# liftsensor.net
KiCad netlist of a schematic drawn in EAGLE
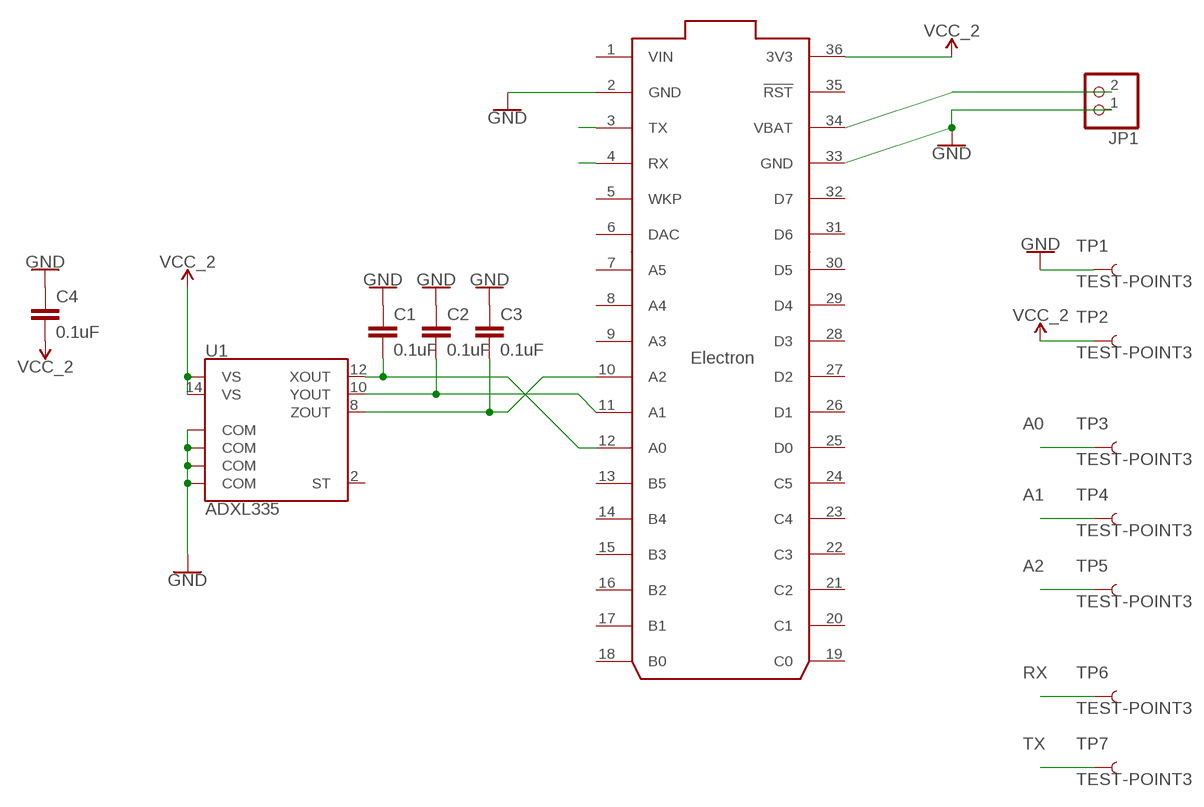
[diagram p0: schematic, sheet 1]

(export (version "E")
  (design (tool "Eeschema 10.0.6"))
  (components
    (comp (ref "C1")
      (value "0.1uF")
      (footprint "eagle-import:0603")
      (libsource (lib "eagle-import") (part "0.1UF-0603-25V-5%"))
    )
    (comp (ref "C2")
      (value "0.1uF")
      (footprint "eagle-import:0603")
      (libsource (lib "eagle-import") (part "0.1UF-0603-25V-5%"))
    )
    (comp (ref "C3")
      (value "0.1uF")
      (footprint "eagle-import:0603")
      (libsource (lib "eagle-import") (part "0.1UF-0603-25V-5%"))
    )
    (comp (ref "C4")
      (value "0.1uF")
      (footprint "eagle-import:0603")
      (libsource (lib "eagle-import") (part "0.1UF-0603-25V-5%"))
    )
    (comp (ref "EL")
      (value "ELECTRON_WITH_HEADERS")
      (footprint "eagle-import:ELECTRON")
      (libsource (lib "eagle-import") (part "ELECTRON_WITH_HEADERS"))
    )
    (comp (ref "JP1")
      (value "PINHD-1X2/90")
      (footprint "eagle-import:1X02_90")
      (libsource (lib "eagle-import") (part "PINHD-1X2/90"))
    )
    (comp (ref "TP1")
      (value "TEST-POINT3")
      (footprint "eagle-import:PAD.03X.03")
      (libsource (lib "eagle-import") (part "TEST-POINT3"))
    )
    (comp (ref "TP2")
      (value "TEST-POINT3")
      (footprint "eagle-import:PAD.03X.03")
      (libsource (lib "eagle-import") (part "TEST-POINT3"))
    )
    (comp (ref "TP3")
      (value "TEST-POINT3")
      (footprint "eagle-import:PAD.03X.03")
      (libsource (lib "eagle-import") (part "TEST-POINT3"))
    )
    (comp (ref "TP4")
      (value "TEST-POINT3")
      (footprint "eagle-import:PAD.03X.03")
      (libsource (lib "eagle-import") (part "TEST-POINT3"))
    )
    (comp (ref "TP5")
      (value "TEST-POINT3")
      (footprint "eagle-import:PAD.03X.03")
      (libsource (lib "eagle-import") (part "TEST-POINT3"))
    )
    (comp (ref "TP6")
      (value "TEST-POINT3")
      (footprint "eagle-import:PAD.03X.03")
      (libsource (lib "eagle-import") (part "TEST-POINT3"))
    )
    (comp (ref "TP7")
      (value "TEST-POINT3")
      (footprint "eagle-import:PAD.03X.03")
      (libsource (lib "eagle-import") (part "TEST-POINT3"))
    )
    (comp (ref "U1")
      (value "ADXL335")
      (footprint "eagle-import:LFCSP-16-4X4")
      (libsource (lib "eagle-import") (part "ADXL335"))
    )
  )
  (nets
    (net (code "1") (name "/A0") (class "Default")
      (node (ref "C1") (pin "2") (pinfunction "2_2") (pintype "passive"))
      (node (ref "EL") (pin "12") (pinfunction "A0_12") (pintype "bidirectional"))
      (node (ref "TP3") (pin "P$1") (pinfunction "1_P$1") (pintype "bidirectional"))
      (node (ref "U1") (pin "12") (pinfunction "XOUT_12") (pintype "bidirectional"))
    )
    (net (code "2") (name "/A1") (class "Default")
      (node (ref "C2") (pin "2") (pinfunction "2_2") (pintype "passive"))
      (node (ref "EL") (pin "11") (pinfunction "A1_11") (pintype "bidirectional"))
      (node (ref "TP4") (pin "P$1") (pinfunction "1_P$1") (pintype "bidirectional"))
      (node (ref "U1") (pin "10") (pinfunction "YOUT_10") (pintype "bidirectional"))
    )
    (net (code "3") (name "/A2") (class "Default")
      (node (ref "C3") (pin "2") (pinfunction "2_2") (pintype "passive"))
      (node (ref "EL") (pin "10") (pinfunction "A2_10") (pintype "bidirectional"))
      (node (ref "TP5") (pin "P$1") (pinfunction "1_P$1") (pintype "bidirectional"))
      (node (ref "U1") (pin "8") (pinfunction "ZOUT_8") (pintype "bidirectional"))
    )
    (net (code "4") (name "/RX") (class "Default")
      (node (ref "EL") (pin "4") (pinfunction "RX_4") (pintype "bidirectional"))
      (node (ref "TP6") (pin "P$1") (pinfunction "1_P$1") (pintype "bidirectional"))
    )
    (net (code "5") (name "/TX") (class "Default")
      (node (ref "EL") (pin "3") (pinfunction "TX_3") (pintype "bidirectional"))
      (node (ref "TP7") (pin "P$1") (pinfunction "1_P$1") (pintype "bidirectional"))
    )
    (net (code "6") (name "/VIN") (class "Default")
      (node (ref "EL") (pin "1") (pinfunction "VIN_1") (pintype "power_in"))
    )
    (net (code "7") (name "GND") (class "Default")
      (node (ref "C1") (pin "1") (pinfunction "1_1") (pintype "passive"))
      (node (ref "C2") (pin "1") (pinfunction "1_1") (pintype "passive"))
      (node (ref "C3") (pin "1") (pinfunction "1_1") (pintype "passive"))
      (node (ref "C4") (pin "1") (pinfunction "1_1") (pintype "passive"))
      (node (ref "EL") (pin "2") (pinfunction "GND_2") (pintype "power_in"))
      (node (ref "EL") (pin "33") (pinfunction "GND_33") (pintype "power_in"))
      (node (ref "JP1") (pin "1") (pinfunction "1_1") (pintype "passive"))
      (node (ref "TP1") (pin "P$1") (pinfunction "1_P$1") (pintype "bidirectional"))
      (node (ref "U1") (pin "3") (pinfunction "COM_3") (pintype "bidirectional"))
      (node (ref "U1") (pin "5") (pinfunction "COM_5") (pintype "bidirectional"))
      (node (ref "U1") (pin "6") (pinfunction "COM_6") (pintype "bidirectional"))
      (node (ref "U1") (pin "7") (pinfunction "COM_7") (pintype "bidirectional"))
    )
    (net (code "8") (name "Net-(EL-VBAT)") (class "Default")
      (node (ref "EL") (pin "34") (pinfunction "VBAT_34") (pintype "power_in"))
      (node (ref "JP1") (pin "2") (pinfunction "2_2") (pintype "passive"))
    )
    (net (code "9") (name "VCC_2") (class "Default")
      (node (ref "C4") (pin "2") (pinfunction "2_2") (pintype "passive"))
      (node (ref "EL") (pin "36") (pinfunction "3V3_36") (pintype "power_in"))
      (node (ref "TP2") (pin "P$1") (pinfunction "1_P$1") (pintype "bidirectional"))
      (node (ref "U1") (pin "14") (pinfunction "VS_14") (pintype "bidirectional"))
      (node (ref "U1") (pin "15") (pinfunction "VS_15") (pintype "bidirectional"))
    )
    (net (code "10") (name "unconnected-(EL-A3-Pad9)") (class "Default")
      (node (ref "EL") (pin "9") (pinfunction "A3_9") (pintype "bidirectional"))
    )
    (net (code "11") (name "unconnected-(EL-A4-Pad8)") (class "Default")
      (node (ref "EL") (pin "8") (pinfunction "A4_8") (pintype "bidirectional"))
    )
    (net (code "12") (name "unconnected-(EL-A5-Pad7)") (class "Default")
      (node (ref "EL") (pin "7") (pinfunction "A5_7") (pintype "bidirectional"))
    )
    (net (code "13") (name "unconnected-(EL-B0-Pad18)") (class "Default")
      (node (ref "EL") (pin "18") (pinfunction "B0_18") (pintype "bidirectional"))
    )
    (net (code "14") (name "unconnected-(EL-B1-Pad17)") (class "Default")
      (node (ref "EL") (pin "17") (pinfunction "B1_17") (pintype "bidirectional"))
    )
    (net (code "15") (name "unconnected-(EL-B2-Pad16)") (class "Default")
      (node (ref "EL") (pin "16") (pinfunction "B2_16") (pintype "bidirectional"))
    )
    (net (code "16") (name "unconnected-(EL-B3-Pad15)") (class "Default")
      (node (ref "EL") (pin "15") (pinfunction "B3_15") (pintype "bidirectional"))
    )
    (net (code "17") (name "unconnected-(EL-B4-Pad14)") (class "Default")
      (node (ref "EL") (pin "14") (pinfunction "B4_14") (pintype "bidirectional"))
    )
    (net (code "18") (name "unconnected-(EL-B5-Pad13)") (class "Default")
      (node (ref "EL") (pin "13") (pinfunction "B5_13") (pintype "bidirectional"))
    )
    (net (code "19") (name "unconnected-(EL-C0-Pad19)") (class "Default")
      (node (ref "EL") (pin "19") (pinfunction "C0_19") (pintype "bidirectional"))
    )
    (net (code "20") (name "unconnected-(EL-C1-Pad20)") (class "Default")
      (node (ref "EL") (pin "20") (pinfunction "C1_20") (pintype "bidirectional"))
    )
    (net (code "21") (name "unconnected-(EL-C2-Pad21)") (class "Default")
      (node (ref "EL") (pin "21") (pinfunction "C2_21") (pintype "bidirectional"))
    )
    (net (code "22") (name "unconnected-(EL-C3-Pad22)") (class "Default")
      (node (ref "EL") (pin "22") (pinfunction "C3_22") (pintype "bidirectional"))
    )
    (net (code "23") (name "unconnected-(EL-C4-Pad23)") (class "Default")
      (node (ref "EL") (pin "23") (pinfunction "C4_23") (pintype "bidirectional"))
    )
    (net (code "24") (name "unconnected-(EL-C5-Pad24)") (class "Default")
      (node (ref "EL") (pin "24") (pinfunction "C5_24") (pintype "bidirectional"))
    )
    (net (code "25") (name "unconnected-(EL-D0-Pad25)") (class "Default")
      (node (ref "EL") (pin "25") (pinfunction "D0_25") (pintype "bidirectional"))
    )
    (net (code "26") (name "unconnected-(EL-D1-Pad26)") (class "Default")
      (node (ref "EL") (pin "26") (pinfunction "D1_26") (pintype "bidirectional"))
    )
    (net (code "27") (name "unconnected-(EL-D2-Pad27)") (class "Default")
      (node (ref "EL") (pin "27") (pinfunction "D2_27") (pintype "bidirectional"))
    )
    (net (code "28") (name "unconnected-(EL-D3-Pad28)") (class "Default")
      (node (ref "EL") (pin "28") (pinfunction "D3_28") (pintype "bidirectional"))
    )
    (net (code "29") (name "unconnected-(EL-D4-Pad29)") (class "Default")
      (node (ref "EL") (pin "29") (pinfunction "D4_29") (pintype "bidirectional"))
    )
    (net (code "30") (name "unconnected-(EL-D5-Pad30)") (class "Default")
      (node (ref "EL") (pin "30") (pinfunction "D5_30") (pintype "bidirectional"))
    )
    (net (code "31") (name "unconnected-(EL-D6-Pad31)") (class "Default")
      (node (ref "EL") (pin "31") (pinfunction "D6_31") (pintype "bidirectional"))
    )
    (net (code "32") (name "unconnected-(EL-D7-Pad32)") (class "Default")
      (node (ref "EL") (pin "32") (pinfunction "D7_32") (pintype "bidirectional"))
    )
    (net (code "33") (name "unconnected-(EL-DAC-Pad6)") (class "Default")
      (node (ref "EL") (pin "6") (pinfunction "DAC_6") (pintype "bidirectional"))
    )
    (net (code "34") (name "unconnected-(EL-WKP-Pad5)") (class "Default")
      (node (ref "EL") (pin "5") (pinfunction "WKP_5") (pintype "bidirectional"))
    )
    (net (code "35") (name "unconnected-(EL-~{RST}-Pad35)") (class "Default")
      (node (ref "EL") (pin "35") (pinfunction "~{RST}_35") (pintype "bidirectional"))
    )
    (net (code "36") (name "unconnected-(U1-ST-Pad2)") (class "Default")
      (node (ref "U1") (pin "2") (pinfunction "ST_2") (pintype "bidirectional"))
    )
  )
)
